# e-Tapperhandpiece31.net
KiCad netlist of a schematic drawn in EAGLE
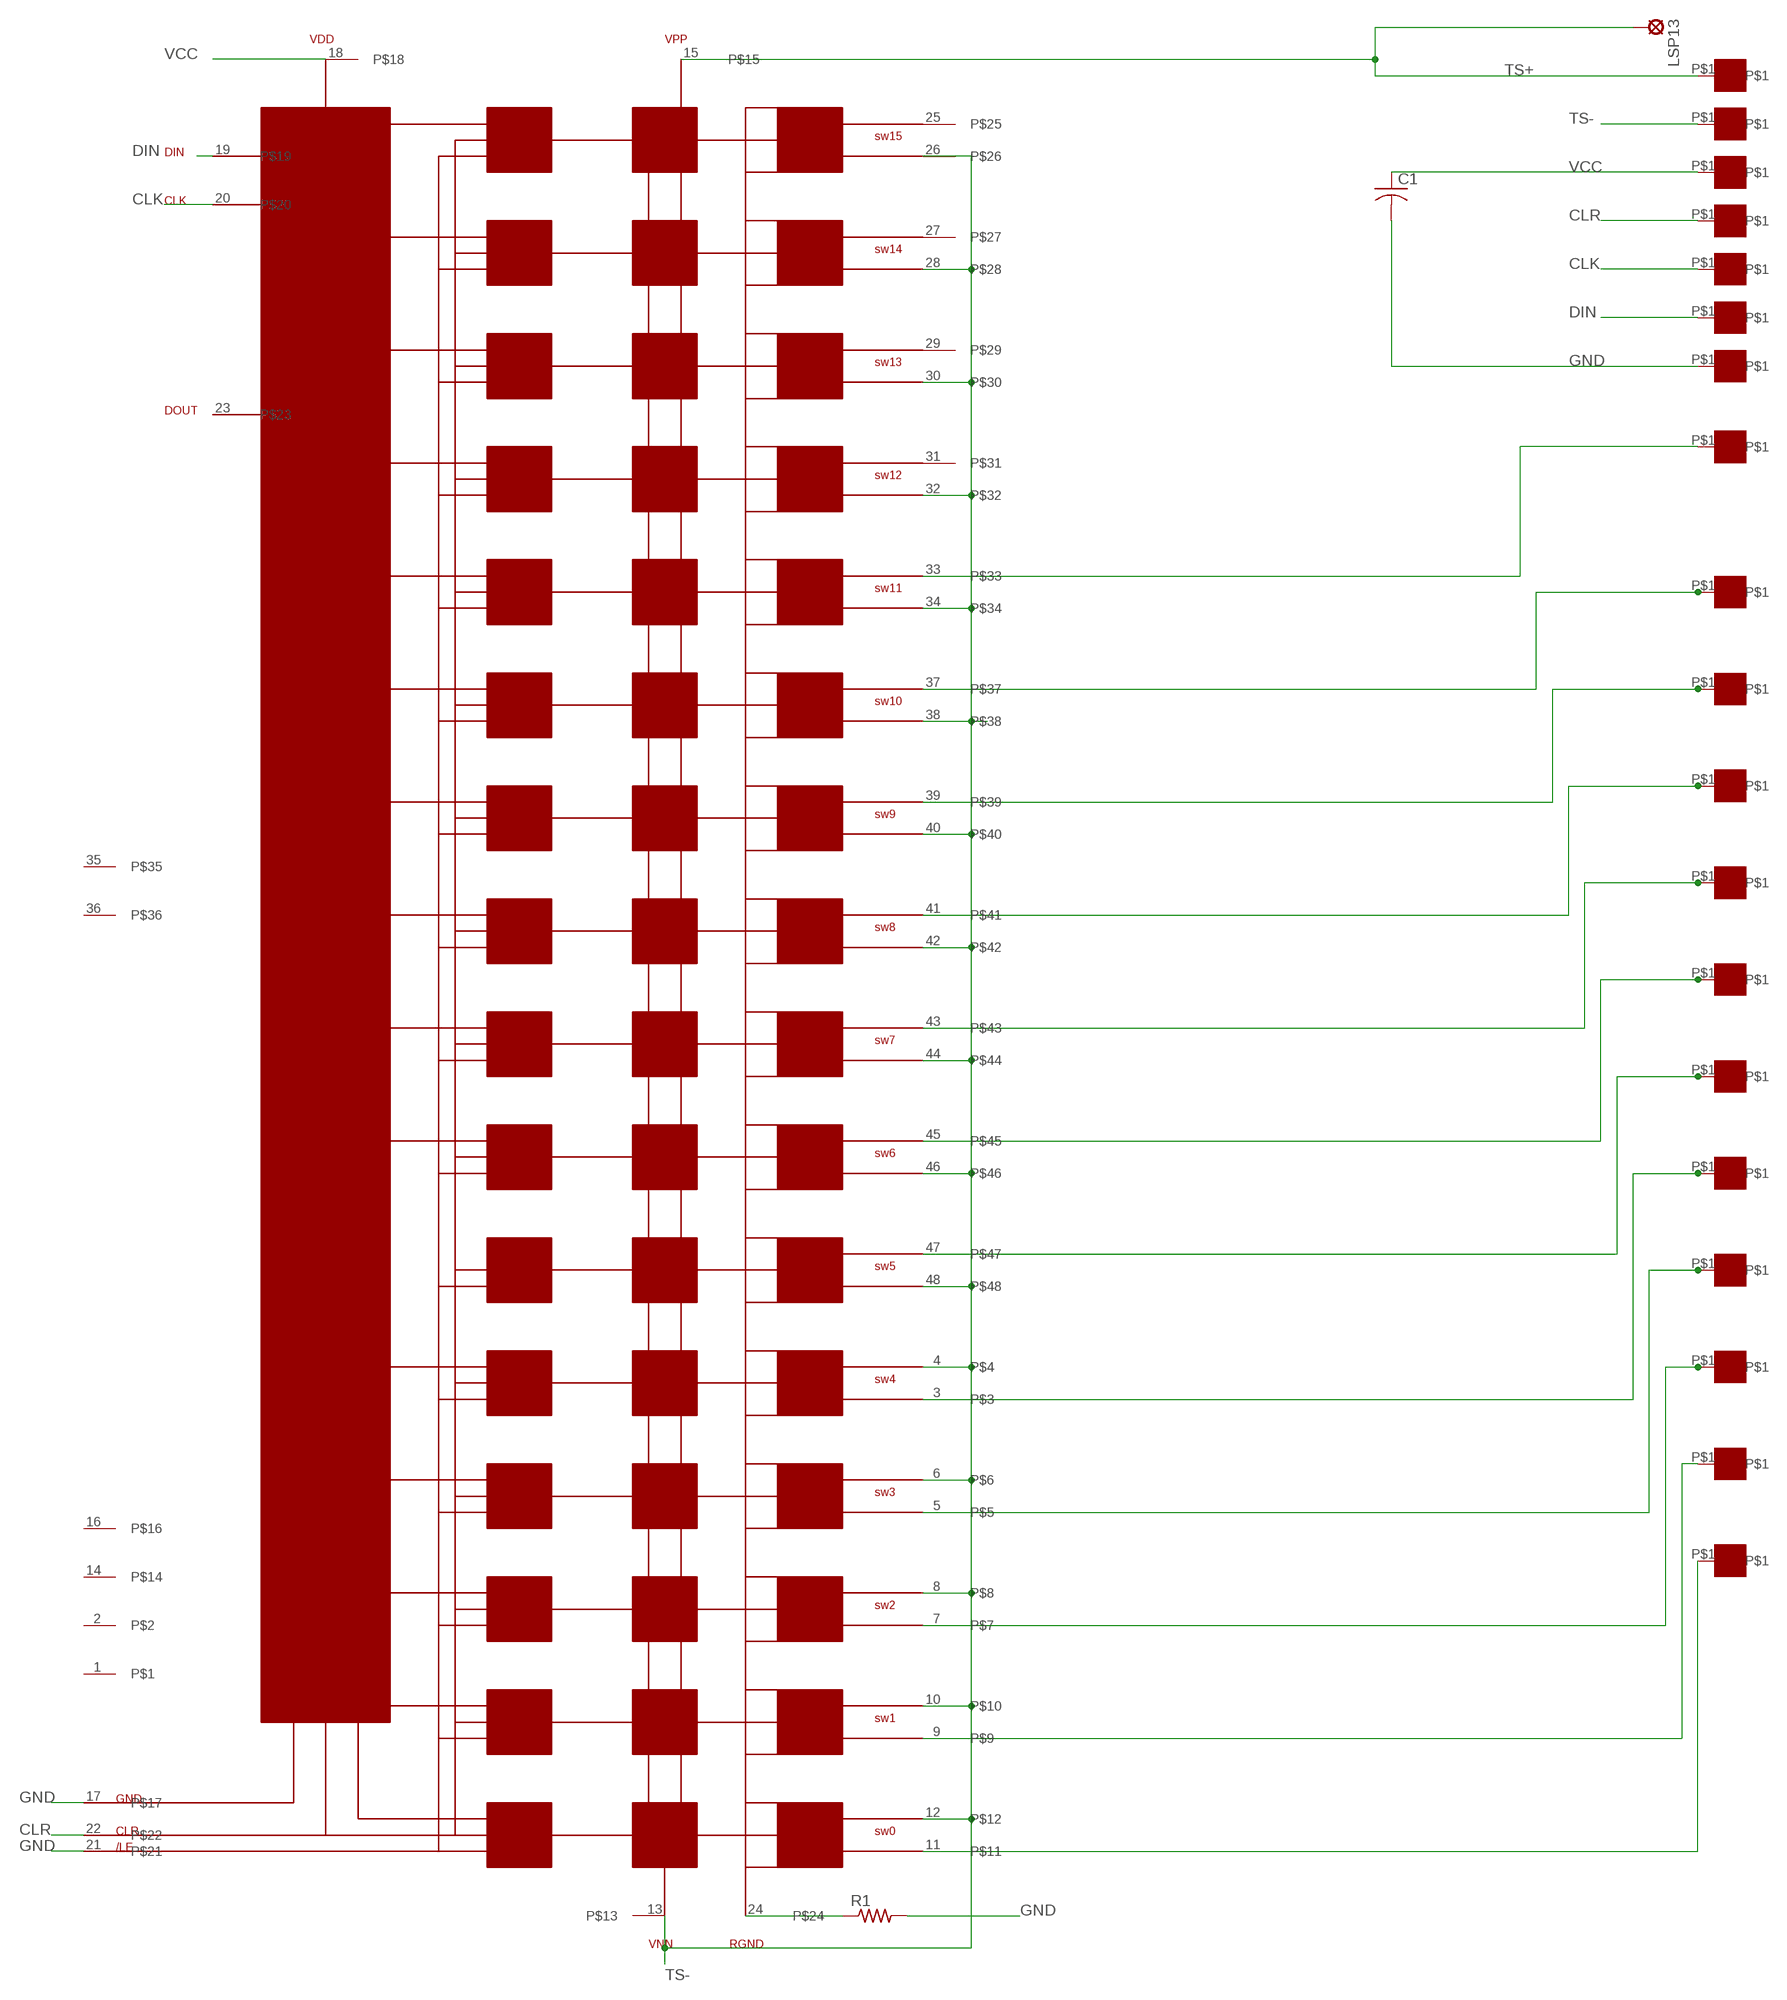
[diagram p0: schematic, sheet 1]

(export (version "E")
  (design (tool "Eeschema 10.0.6"))
  (components
    (comp (ref "C1")
      (value "C-USC0805")
      (footprint "eagle-import:C0805")
      (libsource (lib "eagle-import") (part "C-USC0805"))
    )
    (comp (ref "LSP13")
      (value "SE11")
      (footprint "eagle-import:SE11")
      (libsource (lib "eagle-import") (part "SE11"))
    )
    (comp (ref "R1")
      (value "R-US_R0805")
      (footprint "eagle-import:R0805")
      (libsource (lib "eagle-import") (part "R-US_R0805"))
    )
    (comp (ref "TSP1")
      (value "ET1")
      (footprint "eagle-import:ET1")
      (libsource (lib "eagle-import") (part "ET1"))
    )
    (comp (ref "TSP2")
      (value "ET1")
      (footprint "eagle-import:ET1")
      (libsource (lib "eagle-import") (part "ET1"))
    )
    (comp (ref "TSP3")
      (value "ET1")
      (footprint "eagle-import:ET1")
      (libsource (lib "eagle-import") (part "ET1"))
    )
    (comp (ref "TSP4")
      (value "ET1")
      (footprint "eagle-import:ET1")
      (libsource (lib "eagle-import") (part "ET1"))
    )
    (comp (ref "TSP5")
      (value "ET1")
      (footprint "eagle-import:ET1")
      (libsource (lib "eagle-import") (part "ET1"))
    )
    (comp (ref "TSP6")
      (value "ET1")
      (footprint "eagle-import:ET1")
      (libsource (lib "eagle-import") (part "ET1"))
    )
    (comp (ref "TSP7")
      (value "ET1")
      (footprint "eagle-import:ET1")
      (libsource (lib "eagle-import") (part "ET1"))
    )
    (comp (ref "TSP8")
      (value "ET1")
      (footprint "eagle-import:ET1")
      (libsource (lib "eagle-import") (part "ET1"))
    )
    (comp (ref "TSP9")
      (value "ET1")
      (footprint "eagle-import:ET1")
      (libsource (lib "eagle-import") (part "ET1"))
    )
    (comp (ref "TSP10")
      (value "ET1")
      (footprint "eagle-import:ET1")
      (libsource (lib "eagle-import") (part "ET1"))
    )
    (comp (ref "TSP11")
      (value "ET1")
      (footprint "eagle-import:ET1")
      (libsource (lib "eagle-import") (part "ET1"))
    )
    (comp (ref "TSP12")
      (value "ET1")
      (footprint "eagle-import:ET1")
      (libsource (lib "eagle-import") (part "ET1"))
    )
    (comp (ref "TSP13")
      (value "ET1")
      (footprint "eagle-import:ET1")
      (libsource (lib "eagle-import") (part "ET1"))
    )
    (comp (ref "TSP14")
      (value "ET1")
      (footprint "eagle-import:ET1")
      (libsource (lib "eagle-import") (part "ET1"))
    )
    (comp (ref "TSP16")
      (value "ET1")
      (footprint "eagle-import:ET1")
      (libsource (lib "eagle-import") (part "ET1"))
    )
    (comp (ref "TSP17")
      (value "ET1")
      (footprint "eagle-import:ET1")
      (libsource (lib "eagle-import") (part "ET1"))
    )
    (comp (ref "TSP18")
      (value "ET1")
      (footprint "eagle-import:ET1")
      (libsource (lib "eagle-import") (part "ET1"))
    )
    (comp (ref "TSP19")
      (value "ET1")
      (footprint "eagle-import:ET1")
      (libsource (lib "eagle-import") (part "ET1"))
    )
    (comp (ref "U1")
      (value "CPC7701")
      (footprint "eagle-import:LQFP48")
      (libsource (lib "eagle-import") (part "CPC7701"))
    )
    (comp (ref "VCC")
      (value "ET1")
      (footprint "eagle-import:ET1")
      (libsource (lib "eagle-import") (part "ET1"))
    )
  )
  (nets
    (net (code "1") (name "/CLK") (class "Default")
      (node (ref "TSP17") (pin "P$1") (pinfunction "P$1_P$1") (pintype "bidirectional"))
      (node (ref "U1") (pin "20") (pinfunction "P$20_20") (pintype "bidirectional"))
    )
    (net (code "2") (name "/CLR") (class "Default")
      (node (ref "TSP18") (pin "P$1") (pinfunction "P$1_P$1") (pintype "bidirectional"))
      (node (ref "U1") (pin "22") (pinfunction "P$22_22") (pintype "bidirectional"))
    )
    (net (code "3") (name "/DIN") (class "Default")
      (node (ref "TSP16") (pin "P$1") (pinfunction "P$1_P$1") (pintype "bidirectional"))
      (node (ref "U1") (pin "19") (pinfunction "P$19_19") (pintype "bidirectional"))
    )
    (net (code "4") (name "/GND") (class "Default")
      (node (ref "C1") (pin "2") (pinfunction "2_2") (pintype "passive"))
      (node (ref "R1") (pin "2") (pinfunction "2_2") (pintype "passive"))
      (node (ref "TSP19") (pin "P$1") (pinfunction "P$1_P$1") (pintype "bidirectional"))
      (node (ref "U1") (pin "17") (pinfunction "P$17_17") (pintype "bidirectional"))
      (node (ref "U1") (pin "21") (pinfunction "P$21_21") (pintype "bidirectional"))
    )
    (net (code "5") (name "/TS+") (class "Default")
      (node (ref "LSP13") (pin "MP") (pinfunction "MP_MP") (pintype "passive"))
      (node (ref "TSP13") (pin "P$1") (pinfunction "P$1_P$1") (pintype "bidirectional"))
      (node (ref "U1") (pin "15") (pinfunction "P$15_15") (pintype "bidirectional"))
    )
    (net (code "6") (name "/TS-") (class "Default")
      (node (ref "TSP14") (pin "P$1") (pinfunction "P$1_P$1") (pintype "bidirectional"))
      (node (ref "U1") (pin "10") (pinfunction "P$10_10") (pintype "bidirectional"))
      (node (ref "U1") (pin "12") (pinfunction "P$12_12") (pintype "bidirectional"))
      (node (ref "U1") (pin "13") (pinfunction "P$13_13") (pintype "bidirectional"))
      (node (ref "U1") (pin "26") (pinfunction "P$26_26") (pintype "bidirectional"))
      (node (ref "U1") (pin "28") (pinfunction "P$28_28") (pintype "bidirectional"))
      (node (ref "U1") (pin "30") (pinfunction "P$30_30") (pintype "bidirectional"))
      (node (ref "U1") (pin "32") (pinfunction "P$32_32") (pintype "bidirectional"))
      (node (ref "U1") (pin "34") (pinfunction "P$34_34") (pintype "bidirectional"))
      (node (ref "U1") (pin "38") (pinfunction "P$38_38") (pintype "bidirectional"))
      (node (ref "U1") (pin "4") (pinfunction "P$4_4") (pintype "bidirectional"))
      (node (ref "U1") (pin "40") (pinfunction "P$40_40") (pintype "bidirectional"))
      (node (ref "U1") (pin "42") (pinfunction "P$42_42") (pintype "bidirectional"))
      (node (ref "U1") (pin "44") (pinfunction "P$44_44") (pintype "bidirectional"))
      (node (ref "U1") (pin "46") (pinfunction "P$46_46") (pintype "bidirectional"))
      (node (ref "U1") (pin "48") (pinfunction "P$48_48") (pintype "bidirectional"))
      (node (ref "U1") (pin "6") (pinfunction "P$6_6") (pintype "bidirectional"))
      (node (ref "U1") (pin "8") (pinfunction "P$8_8") (pintype "bidirectional"))
    )
    (net (code "7") (name "/VCC") (class "Default")
      (node (ref "C1") (pin "1") (pinfunction "1_1") (pintype "passive"))
      (node (ref "U1") (pin "18") (pinfunction "P$18_18") (pintype "bidirectional"))
      (node (ref "VCC") (pin "P$1") (pinfunction "P$1_P$1") (pintype "bidirectional"))
    )
    (net (code "8") (name "Net-(U1-P$3)") (class "Default")
      (node (ref "TSP8") (pin "P$1") (pinfunction "P$1_P$1") (pintype "bidirectional"))
      (node (ref "U1") (pin "3") (pinfunction "P$3_3") (pintype "bidirectional"))
    )
    (net (code "9") (name "Net-(U1-P$5)") (class "Default")
      (node (ref "TSP9") (pin "P$1") (pinfunction "P$1_P$1") (pintype "bidirectional"))
      (node (ref "U1") (pin "5") (pinfunction "P$5_5") (pintype "bidirectional"))
    )
    (net (code "10") (name "Net-(U1-P$7)") (class "Default")
      (node (ref "TSP10") (pin "P$1") (pinfunction "P$1_P$1") (pintype "bidirectional"))
      (node (ref "U1") (pin "7") (pinfunction "P$7_7") (pintype "bidirectional"))
    )
    (net (code "11") (name "Net-(U1-P$9)") (class "Default")
      (node (ref "TSP11") (pin "P$1") (pinfunction "P$1_P$1") (pintype "bidirectional"))
      (node (ref "U1") (pin "9") (pinfunction "P$9_9") (pintype "bidirectional"))
    )
    (net (code "12") (name "Net-(U1-P$11)") (class "Default")
      (node (ref "TSP12") (pin "P$1") (pinfunction "P$1_P$1") (pintype "bidirectional"))
      (node (ref "U1") (pin "11") (pinfunction "P$11_11") (pintype "bidirectional"))
    )
    (net (code "13") (name "Net-(U1-P$24)") (class "Default")
      (node (ref "R1") (pin "1") (pinfunction "1_1") (pintype "passive"))
      (node (ref "U1") (pin "24") (pinfunction "P$24_24") (pintype "bidirectional"))
    )
    (net (code "14") (name "Net-(U1-P$33)") (class "Default")
      (node (ref "TSP1") (pin "P$1") (pinfunction "P$1_P$1") (pintype "bidirectional"))
      (node (ref "U1") (pin "33") (pinfunction "P$33_33") (pintype "bidirectional"))
    )
    (net (code "15") (name "Net-(U1-P$37)") (class "Default")
      (node (ref "TSP2") (pin "P$1") (pinfunction "P$1_P$1") (pintype "bidirectional"))
      (node (ref "U1") (pin "37") (pinfunction "P$37_37") (pintype "bidirectional"))
    )
    (net (code "16") (name "Net-(U1-P$39)") (class "Default")
      (node (ref "TSP3") (pin "P$1") (pinfunction "P$1_P$1") (pintype "bidirectional"))
      (node (ref "U1") (pin "39") (pinfunction "P$39_39") (pintype "bidirectional"))
    )
    (net (code "17") (name "Net-(U1-P$41)") (class "Default")
      (node (ref "TSP4") (pin "P$1") (pinfunction "P$1_P$1") (pintype "bidirectional"))
      (node (ref "U1") (pin "41") (pinfunction "P$41_41") (pintype "bidirectional"))
    )
    (net (code "18") (name "Net-(U1-P$43)") (class "Default")
      (node (ref "TSP5") (pin "P$1") (pinfunction "P$1_P$1") (pintype "bidirectional"))
      (node (ref "U1") (pin "43") (pinfunction "P$43_43") (pintype "bidirectional"))
    )
    (net (code "19") (name "Net-(U1-P$45)") (class "Default")
      (node (ref "TSP6") (pin "P$1") (pinfunction "P$1_P$1") (pintype "bidirectional"))
      (node (ref "U1") (pin "45") (pinfunction "P$45_45") (pintype "bidirectional"))
    )
    (net (code "20") (name "Net-(U1-P$47)") (class "Default")
      (node (ref "TSP7") (pin "P$1") (pinfunction "P$1_P$1") (pintype "bidirectional"))
      (node (ref "U1") (pin "47") (pinfunction "P$47_47") (pintype "bidirectional"))
    )
    (net (code "21") (name "unconnected-(U1-P$1-Pad1)") (class "Default")
      (node (ref "U1") (pin "1") (pinfunction "P$1_1") (pintype "bidirectional"))
    )
    (net (code "22") (name "unconnected-(U1-P$2-Pad2)") (class "Default")
      (node (ref "U1") (pin "2") (pinfunction "P$2_2") (pintype "bidirectional"))
    )
    (net (code "23") (name "unconnected-(U1-P$14-Pad14)") (class "Default")
      (node (ref "U1") (pin "14") (pinfunction "P$14_14") (pintype "bidirectional"))
    )
    (net (code "24") (name "unconnected-(U1-P$16-Pad16)") (class "Default")
      (node (ref "U1") (pin "16") (pinfunction "P$16_16") (pintype "bidirectional"))
    )
    (net (code "25") (name "unconnected-(U1-P$23-Pad23)") (class "Default")
      (node (ref "U1") (pin "23") (pinfunction "P$23_23") (pintype "bidirectional"))
    )
    (net (code "26") (name "unconnected-(U1-P$25-Pad25)") (class "Default")
      (node (ref "U1") (pin "25") (pinfunction "P$25_25") (pintype "bidirectional"))
    )
    (net (code "27") (name "unconnected-(U1-P$27-Pad27)") (class "Default")
      (node (ref "U1") (pin "27") (pinfunction "P$27_27") (pintype "bidirectional"))
    )
    (net (code "28") (name "unconnected-(U1-P$29-Pad29)") (class "Default")
      (node (ref "U1") (pin "29") (pinfunction "P$29_29") (pintype "bidirectional"))
    )
    (net (code "29") (name "unconnected-(U1-P$31-Pad31)") (class "Default")
      (node (ref "U1") (pin "31") (pinfunction "P$31_31") (pintype "bidirectional"))
    )
    (net (code "30") (name "unconnected-(U1-P$35-Pad35)") (class "Default")
      (node (ref "U1") (pin "35") (pinfunction "P$35_35") (pintype "bidirectional"))
    )
    (net (code "31") (name "unconnected-(U1-P$36-Pad36)") (class "Default")
      (node (ref "U1") (pin "36") (pinfunction "P$36_36") (pintype "bidirectional"))
    )
  )
)
